# REFLOW_TOASTER.net
KiCad netlist of a schematic drawn in EAGLE
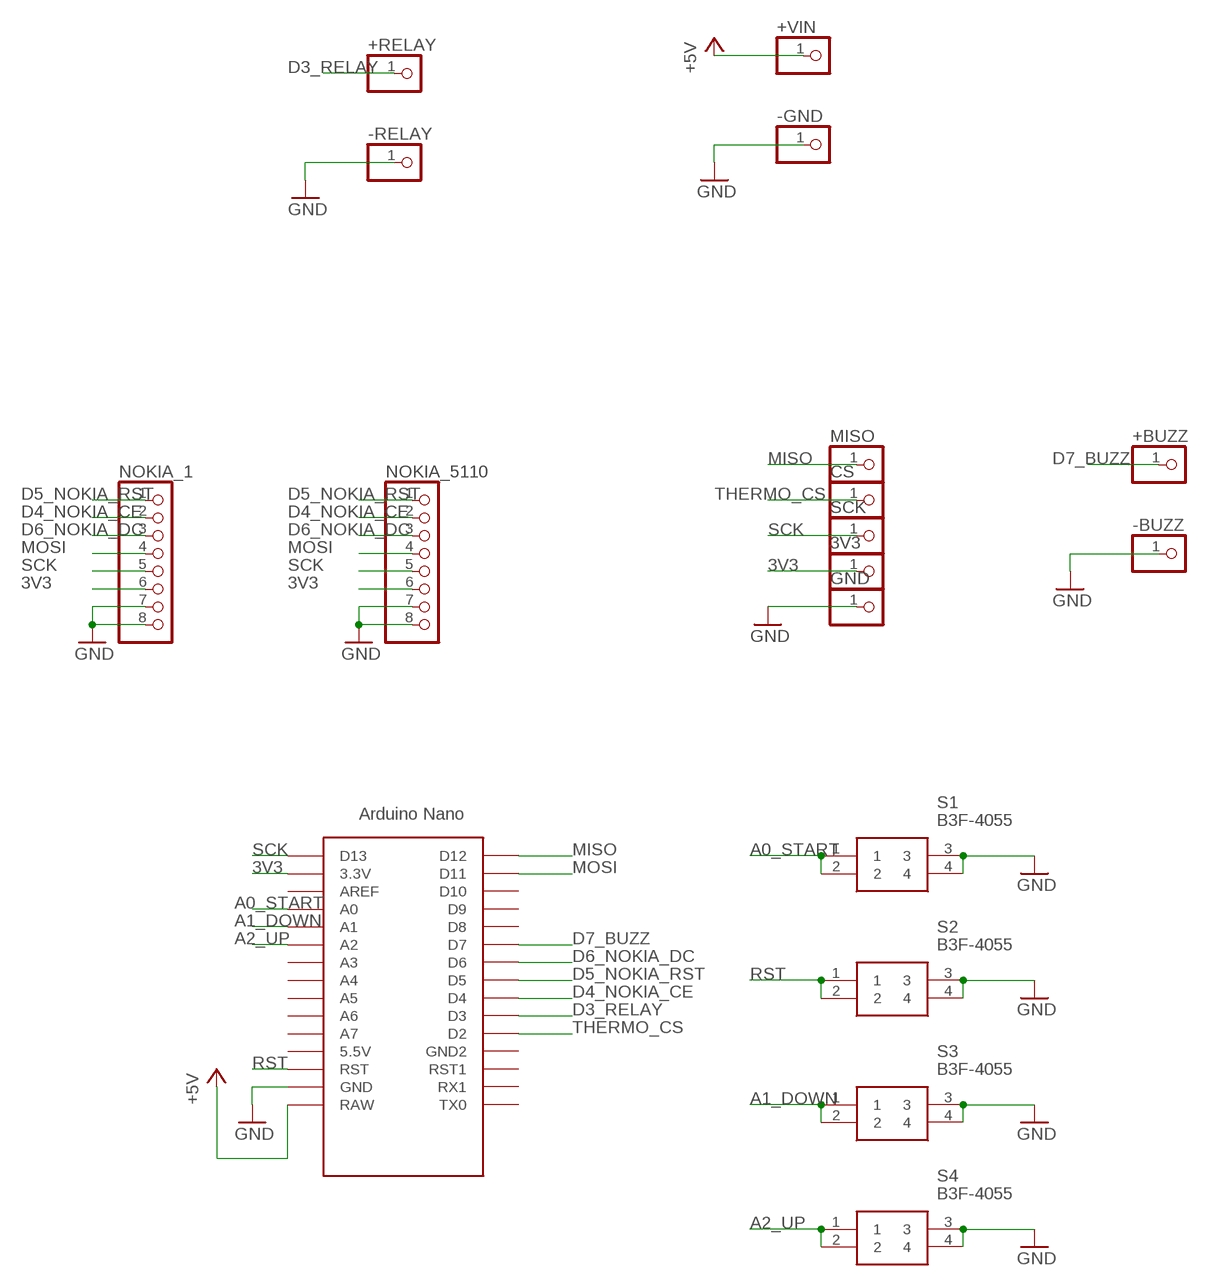
[diagram p0: schematic, sheet 1]

(export (version "E")
  (design (tool "Eeschema 10.0.6"))
  (components
    (comp (ref "+BUZZ")
      (value "PINHD-1X1CB")
      (footprint "eagle-import:1X01-CLEANBIG")
      (libsource (lib "eagle-import") (part "PINHD-1X1CB"))
    )
    (comp (ref "+RELAY")
      (value "PINHD-1X1CB")
      (footprint "eagle-import:1X01-CLEANBIG")
      (libsource (lib "eagle-import") (part "PINHD-1X1CB"))
    )
    (comp (ref "+VIN")
      (value "PINHD-1X1CB")
      (footprint "eagle-import:1X01-CLEANBIG")
      (libsource (lib "eagle-import") (part "PINHD-1X1CB"))
    )
    (comp (ref "-BUZZ")
      (value "PINHD-1X1CB")
      (footprint "eagle-import:1X01-CLEANBIG")
      (libsource (lib "eagle-import") (part "PINHD-1X1CB"))
    )
    (comp (ref "-GND")
      (value "PINHD-1X1CB")
      (footprint "eagle-import:1X01-CLEANBIG")
      (libsource (lib "eagle-import") (part "PINHD-1X1CB"))
    )
    (comp (ref "-RELAY")
      (value "PINHD-1X1CB")
      (footprint "eagle-import:1X01-CLEANBIG")
      (libsource (lib "eagle-import") (part "PINHD-1X1CB"))
    )
    (comp (ref "3V3")
      (value "PINHD-1X1CB")
      (footprint "eagle-import:1X01-CLEANBIG")
      (libsource (lib "eagle-import") (part "PINHD-1X1CB"))
    )
    (comp (ref "CS")
      (value "PINHD-1X1CB")
      (footprint "eagle-import:1X01-CLEANBIG")
      (libsource (lib "eagle-import") (part "PINHD-1X1CB"))
    )
    (comp (ref "GND")
      (value "PINHD-1X1CB")
      (footprint "eagle-import:1X01-CLEANBIG")
      (libsource (lib "eagle-import") (part "PINHD-1X1CB"))
    )
    (comp (ref "MISO")
      (value "PINHD-1X1CB")
      (footprint "eagle-import:1X01-CLEANBIG")
      (libsource (lib "eagle-import") (part "PINHD-1X1CB"))
    )
    (comp (ref "NOKIA_1")
      (value "PINHD-1X8CLEANBIG")
      (footprint "eagle-import:1X08-CLEANBIG")
      (libsource (lib "eagle-import") (part "PINHD-1X8CLEANBIG"))
    )
    (comp (ref "NOKIA_5110")
      (value "PINHD-1X8CLEANBIG")
      (footprint "eagle-import:1X08-CLEANBIG")
      (libsource (lib "eagle-import") (part "PINHD-1X8CLEANBIG"))
    )
    (comp (ref "S1")
      (value "B3F-4055")
      (footprint "eagle-import:B3F-4055")
      (fields (field (name "RS_PART_NUMBER") "6866777P"))
      (libsource (lib "eagle-import") (part "B3F-4055"))
    )
    (comp (ref "S2")
      (value "B3F-4055")
      (footprint "eagle-import:B3F-4055")
      (fields (field (name "RS_PART_NUMBER") "6866777P"))
      (libsource (lib "eagle-import") (part "B3F-4055"))
    )
    (comp (ref "S3")
      (value "B3F-4055")
      (footprint "eagle-import:B3F-4055")
      (fields (field (name "RS_PART_NUMBER") "6866777P"))
      (libsource (lib "eagle-import") (part "B3F-4055"))
    )
    (comp (ref "S4")
      (value "B3F-4055")
      (footprint "eagle-import:B3F-4055")
      (fields (field (name "RS_PART_NUMBER") "6866777P"))
      (libsource (lib "eagle-import") (part "B3F-4055"))
    )
    (comp (ref "SCK")
      (value "PINHD-1X1CB")
      (footprint "eagle-import:1X01-CLEANBIG")
      (libsource (lib "eagle-import") (part "PINHD-1X1CB"))
    )
    (comp (ref "U$1")
      (value "NANO")
      (footprint "eagle-import:NANO")
      (libsource (lib "eagle-import") (part "NANO"))
    )
  )
  (nets
    (net (code "1") (name "+5V") (class "Default")
      (node (ref "+VIN") (pin "1") (pinfunction "1_1") (pintype "passive"))
      (node (ref "U$1") (pin "RAW") (pinfunction "RAW_RAW") (pintype "bidirectional"))
    )
    (net (code "2") (name "/3V3") (class "Default")
      (node (ref "3V3") (pin "1") (pinfunction "1_1") (pintype "passive"))
      (node (ref "NOKIA_1") (pin "6") (pinfunction "6_6") (pintype "passive"))
      (node (ref "NOKIA_5110") (pin "6") (pinfunction "6_6") (pintype "passive"))
      (node (ref "U$1") (pin "3.3V") (pinfunction "3.3V_3.3V") (pintype "bidirectional"))
    )
    (net (code "3") (name "/A0_START") (class "Default")
      (node (ref "S1") (pin "1") (pinfunction "1_1") (pintype "bidirectional"))
      (node (ref "S1") (pin "2") (pinfunction "2_2") (pintype "bidirectional"))
      (node (ref "U$1") (pin "A0") (pinfunction "A0_A0") (pintype "bidirectional"))
    )
    (net (code "4") (name "/A1_DOWN") (class "Default")
      (node (ref "S3") (pin "1") (pinfunction "1_1") (pintype "bidirectional"))
      (node (ref "S3") (pin "2") (pinfunction "2_2") (pintype "bidirectional"))
      (node (ref "U$1") (pin "A1") (pinfunction "A1_A1") (pintype "bidirectional"))
    )
    (net (code "5") (name "/A2_UP") (class "Default")
      (node (ref "S4") (pin "1") (pinfunction "1_1") (pintype "bidirectional"))
      (node (ref "S4") (pin "2") (pinfunction "2_2") (pintype "bidirectional"))
      (node (ref "U$1") (pin "A2") (pinfunction "A2_A2") (pintype "bidirectional"))
    )
    (net (code "6") (name "/D3_RELAY") (class "Default")
      (node (ref "+RELAY") (pin "1") (pinfunction "1_1") (pintype "passive"))
      (node (ref "U$1") (pin "D3") (pinfunction "D3_D3") (pintype "bidirectional"))
    )
    (net (code "7") (name "/D4_NOKIA_CE") (class "Default")
      (node (ref "NOKIA_1") (pin "2") (pinfunction "2_2") (pintype "passive"))
      (node (ref "NOKIA_5110") (pin "2") (pinfunction "2_2") (pintype "passive"))
      (node (ref "U$1") (pin "D4") (pinfunction "D4_D4") (pintype "bidirectional"))
    )
    (net (code "8") (name "/D5_NOKIA_RST") (class "Default")
      (node (ref "NOKIA_1") (pin "1") (pinfunction "1_1") (pintype "passive"))
      (node (ref "NOKIA_5110") (pin "1") (pinfunction "1_1") (pintype "passive"))
      (node (ref "U$1") (pin "D5") (pinfunction "D5_D5") (pintype "bidirectional"))
    )
    (net (code "9") (name "/D6_NOKIA_DC") (class "Default")
      (node (ref "NOKIA_1") (pin "3") (pinfunction "3_3") (pintype "passive"))
      (node (ref "NOKIA_5110") (pin "3") (pinfunction "3_3") (pintype "passive"))
      (node (ref "U$1") (pin "D6") (pinfunction "D6_D6") (pintype "bidirectional"))
    )
    (net (code "10") (name "/D7_BUZZ") (class "Default")
      (node (ref "+BUZZ") (pin "1") (pinfunction "1_1") (pintype "passive"))
      (node (ref "U$1") (pin "D7") (pinfunction "D7_D7") (pintype "bidirectional"))
    )
    (net (code "11") (name "/MISO") (class "Default")
      (node (ref "MISO") (pin "1") (pinfunction "1_1") (pintype "passive"))
      (node (ref "U$1") (pin "D12") (pinfunction "D12_D12") (pintype "bidirectional"))
    )
    (net (code "12") (name "/MOSI") (class "Default")
      (node (ref "NOKIA_1") (pin "4") (pinfunction "4_4") (pintype "passive"))
      (node (ref "NOKIA_5110") (pin "4") (pinfunction "4_4") (pintype "passive"))
      (node (ref "U$1") (pin "D11") (pinfunction "D11_D11") (pintype "bidirectional"))
    )
    (net (code "13") (name "/RST") (class "Default")
      (node (ref "S2") (pin "1") (pinfunction "1_1") (pintype "bidirectional"))
      (node (ref "S2") (pin "2") (pinfunction "2_2") (pintype "bidirectional"))
      (node (ref "U$1") (pin "RST") (pinfunction "RST_RST") (pintype "bidirectional"))
    )
    (net (code "14") (name "/SCK") (class "Default")
      (node (ref "NOKIA_1") (pin "5") (pinfunction "5_5") (pintype "passive"))
      (node (ref "NOKIA_5110") (pin "5") (pinfunction "5_5") (pintype "passive"))
      (node (ref "SCK") (pin "1") (pinfunction "1_1") (pintype "passive"))
      (node (ref "U$1") (pin "D13") (pinfunction "D13_D13") (pintype "bidirectional"))
    )
    (net (code "15") (name "/THERMO_CS") (class "Default")
      (node (ref "CS") (pin "1") (pinfunction "1_1") (pintype "passive"))
      (node (ref "U$1") (pin "D2") (pinfunction "D2_D2") (pintype "bidirectional"))
    )
    (net (code "16") (name "GND") (class "Default")
      (node (ref "-BUZZ") (pin "1") (pinfunction "1_1") (pintype "passive"))
      (node (ref "-GND") (pin "1") (pinfunction "1_1") (pintype "passive"))
      (node (ref "-RELAY") (pin "1") (pinfunction "1_1") (pintype "passive"))
      (node (ref "GND") (pin "1") (pinfunction "1_1") (pintype "passive"))
      (node (ref "NOKIA_1") (pin "7") (pinfunction "7_7") (pintype "passive"))
      (node (ref "NOKIA_1") (pin "8") (pinfunction "8_8") (pintype "passive"))
      (node (ref "NOKIA_5110") (pin "7") (pinfunction "7_7") (pintype "passive"))
      (node (ref "NOKIA_5110") (pin "8") (pinfunction "8_8") (pintype "passive"))
      (node (ref "S1") (pin "3") (pinfunction "3_3") (pintype "bidirectional"))
      (node (ref "S1") (pin "4") (pinfunction "4_4") (pintype "bidirectional"))
      (node (ref "S2") (pin "3") (pinfunction "3_3") (pintype "bidirectional"))
      (node (ref "S2") (pin "4") (pinfunction "4_4") (pintype "bidirectional"))
      (node (ref "S3") (pin "3") (pinfunction "3_3") (pintype "bidirectional"))
      (node (ref "S3") (pin "4") (pinfunction "4_4") (pintype "bidirectional"))
      (node (ref "S4") (pin "3") (pinfunction "3_3") (pintype "bidirectional"))
      (node (ref "S4") (pin "4") (pinfunction "4_4") (pintype "bidirectional"))
      (node (ref "U$1") (pin "GND") (pinfunction "GND_GND") (pintype "bidirectional"))
    )
    (net (code "17") (name "unconnected-(U$1-5.5V-Pad5V)") (class "Default")
      (node (ref "U$1") (pin "5V") (pinfunction "5.5V_5V") (pintype "bidirectional"))
    )
    (net (code "18") (name "unconnected-(U$1-GND2-PadGND1)") (class "Default")
      (node (ref "U$1") (pin "GND1") (pinfunction "GND2_GND1") (pintype "bidirectional"))
    )
    (net (code "19") (name "unconnected-(U$1-PadA3)") (class "Default")
      (node (ref "U$1") (pin "A3") (pinfunction "A3_A3") (pintype "bidirectional"))
    )
    (net (code "20") (name "unconnected-(U$1-PadA4)") (class "Default")
      (node (ref "U$1") (pin "A4") (pinfunction "A4_A4") (pintype "bidirectional"))
    )
    (net (code "21") (name "unconnected-(U$1-PadA5)") (class "Default")
      (node (ref "U$1") (pin "A5") (pinfunction "A5_A5") (pintype "bidirectional"))
    )
    (net (code "22") (name "unconnected-(U$1-PadA6)") (class "Default")
      (node (ref "U$1") (pin "A6") (pinfunction "A6_A6") (pintype "bidirectional"))
    )
    (net (code "23") (name "unconnected-(U$1-PadA7)") (class "Default")
      (node (ref "U$1") (pin "A7") (pinfunction "A7_A7") (pintype "bidirectional"))
    )
    (net (code "24") (name "unconnected-(U$1-PadAREF)") (class "Default")
      (node (ref "U$1") (pin "AREF") (pinfunction "AREF_AREF") (pintype "bidirectional"))
    )
    (net (code "25") (name "unconnected-(U$1-PadD8)") (class "Default")
      (node (ref "U$1") (pin "D8") (pinfunction "D8_D8") (pintype "bidirectional"))
    )
    (net (code "26") (name "unconnected-(U$1-PadD9)") (class "Default")
      (node (ref "U$1") (pin "D9") (pinfunction "D9_D9") (pintype "bidirectional"))
    )
    (net (code "27") (name "unconnected-(U$1-PadD10)") (class "Default")
      (node (ref "U$1") (pin "D10") (pinfunction "D10_D10") (pintype "bidirectional"))
    )
    (net (code "28") (name "unconnected-(U$1-PadICSP1)") (class "Default")
      (node (ref "U$1") (pin "ICSP1") (pinfunction "ICSP1_ICSP1") (pintype "bidirectional"))
    )
    (net (code "29") (name "unconnected-(U$1-PadICSP2)") (class "Default")
      (node (ref "U$1") (pin "ICSP2") (pinfunction "ICSP2_ICSP2") (pintype "bidirectional"))
    )
    (net (code "30") (name "unconnected-(U$1-PadICSP3)") (class "Default")
      (node (ref "U$1") (pin "ICSP3") (pinfunction "ICSP3_ICSP3") (pintype "bidirectional"))
    )
    (net (code "31") (name "unconnected-(U$1-PadICSP4)") (class "Default")
      (node (ref "U$1") (pin "ICSP4") (pinfunction "ICSP4_ICSP4") (pintype "bidirectional"))
    )
    (net (code "32") (name "unconnected-(U$1-PadICSP5)") (class "Default")
      (node (ref "U$1") (pin "ICSP5") (pinfunction "ICSP5_ICSP5") (pintype "bidirectional"))
    )
    (net (code "33") (name "unconnected-(U$1-PadICSP6)") (class "Default")
      (node (ref "U$1") (pin "ICSP6") (pinfunction "ICSP6_ICSP6") (pintype "bidirectional"))
    )
    (net (code "34") (name "unconnected-(U$1-PadRST1)") (class "Default")
      (node (ref "U$1") (pin "RST1") (pinfunction "RST1_RST1") (pintype "bidirectional"))
    )
    (net (code "35") (name "unconnected-(U$1-PadRX1)") (class "Default")
      (node (ref "U$1") (pin "RX1") (pinfunction "RX1_RX1") (pintype "bidirectional"))
    )
    (net (code "36") (name "unconnected-(U$1-PadTX0)") (class "Default")
      (node (ref "U$1") (pin "TX0") (pinfunction "TX0_TX0") (pintype "bidirectional"))
    )
  )
)
